# client.net
KiCad netlist of a schematic drawn in Altium Designer
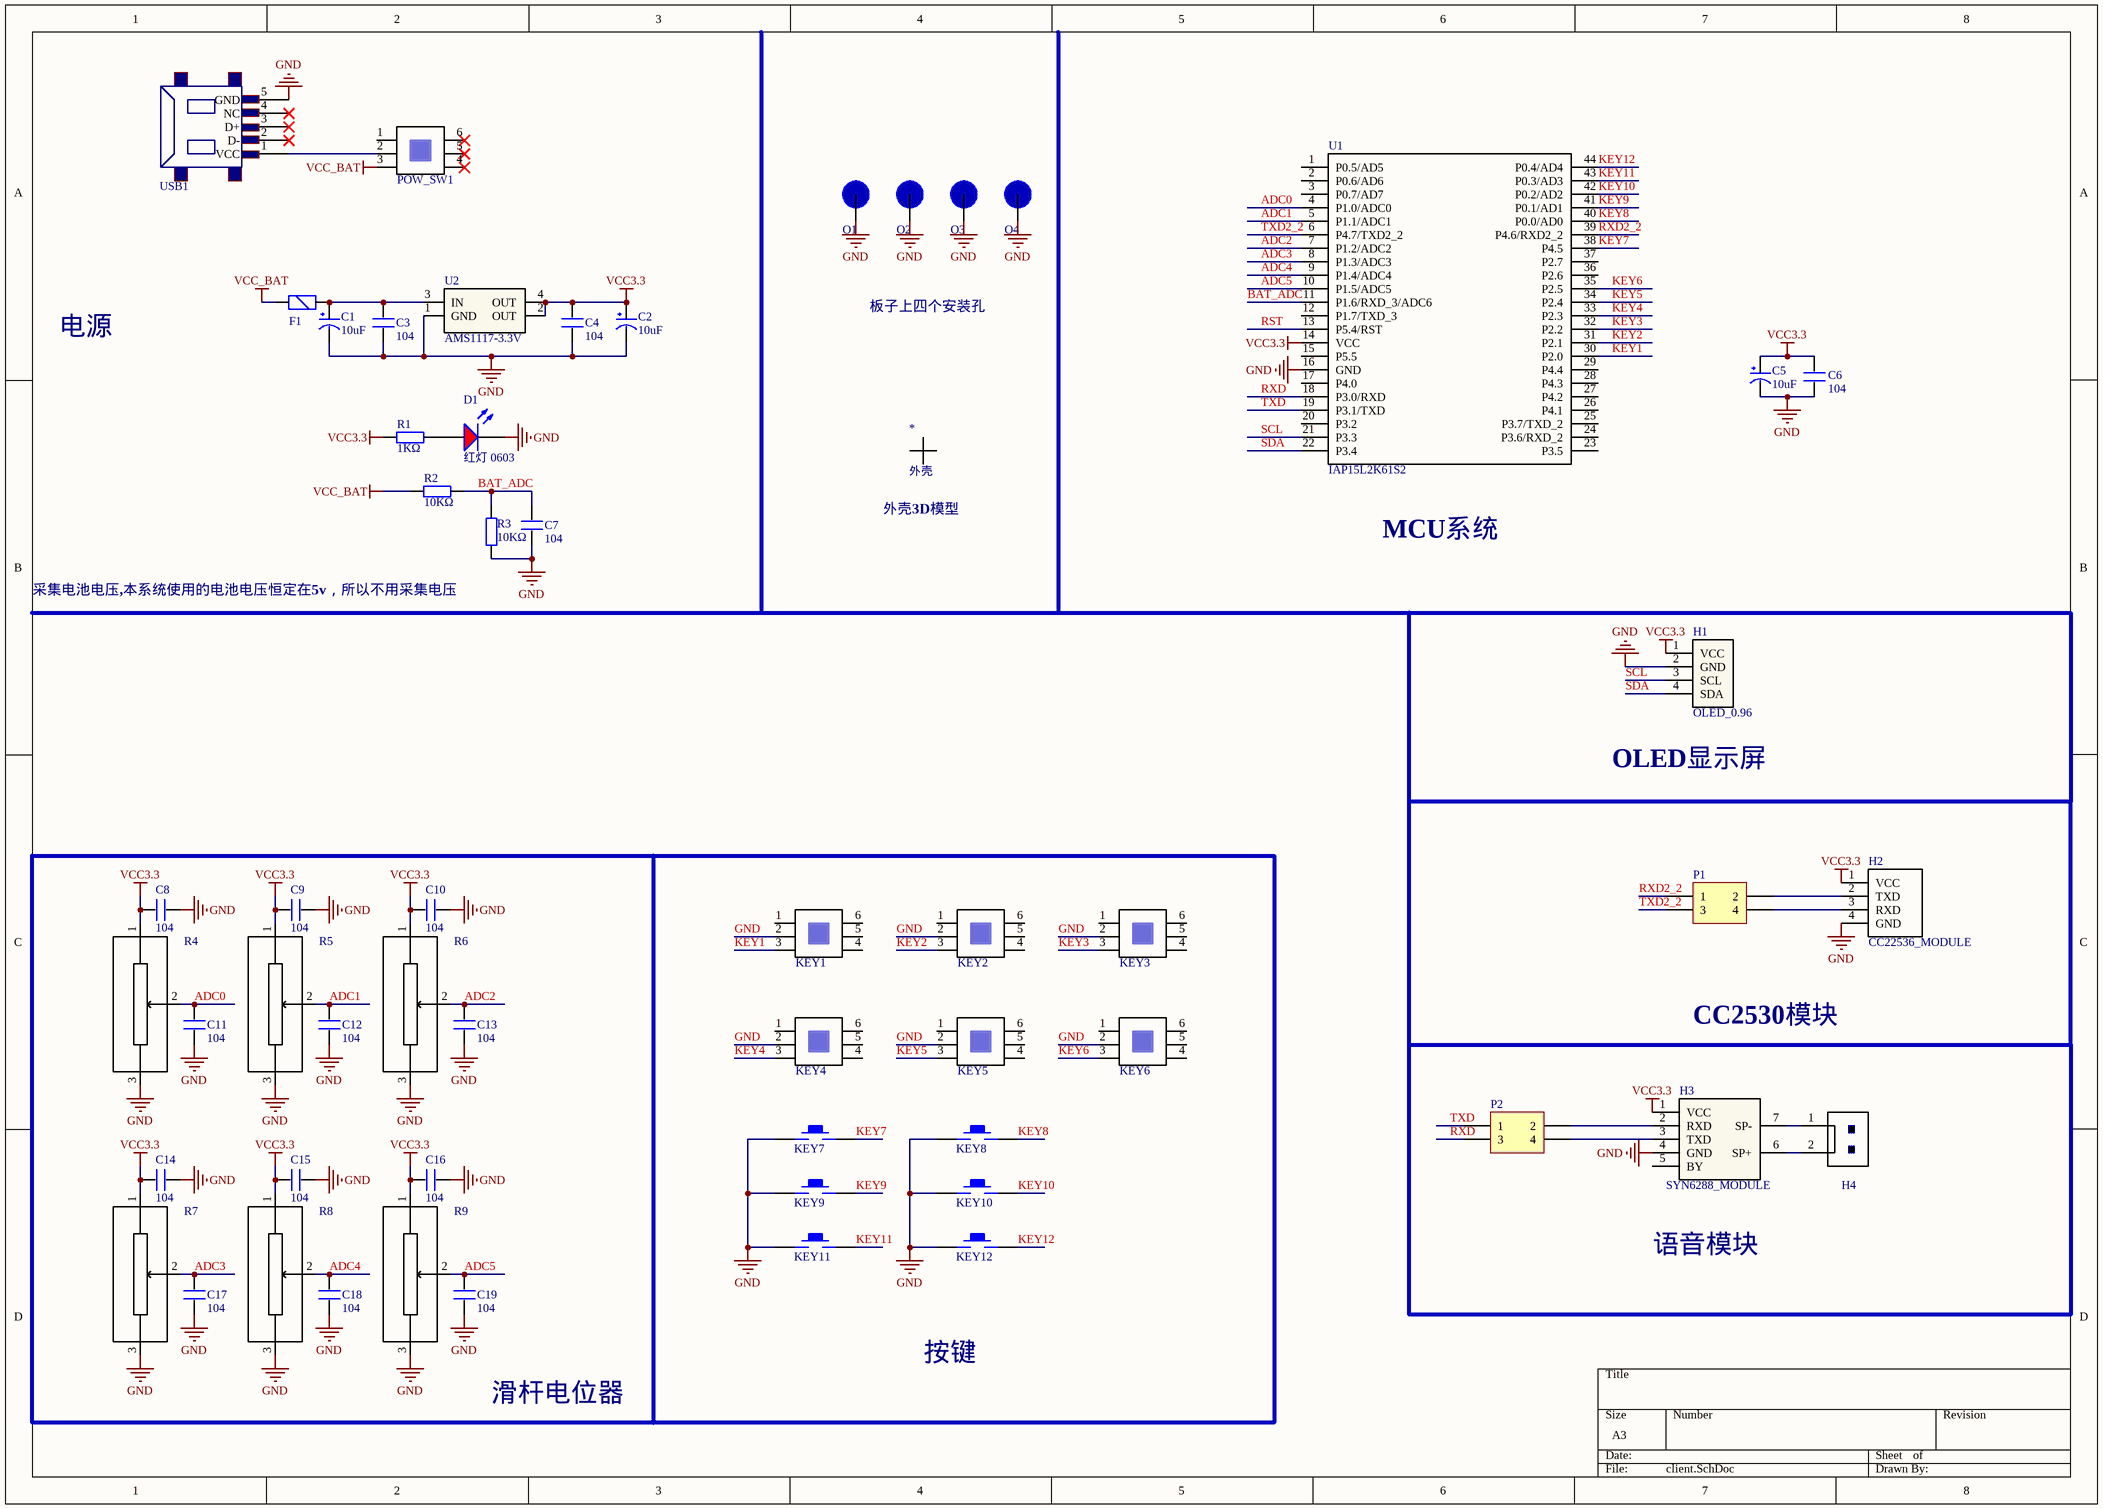
[diagram p0: client.SchDoc]

(export (version "E")
  (design (tool "Eeschema 10.0.6"))
  (components
    (comp (ref "*") (value "外壳") (footprint "MYLIB:外壳") (libsource (lib "mylib") (part "外壳")))
    (comp (ref "C1")
      (value "10uF")
      (footprint "3D common:C4X4")
      (libsource (lib "WarShip V3 STM32103封装库") (part "CAP"))
    )
    (comp (ref "C2")
      (value "10uF")
      (footprint "3D common:C4X4")
      (libsource (lib "WarShip V3 STM32103封装库") (part "CAP"))
    )
    (comp (ref "C3")
      (value "104")
      (footprint "嘉立创库:0603_C")
      (libsource (lib "WarShip V3 STM32103封装库") (part "C"))
    )
    (comp (ref "C4")
      (value "104")
      (footprint "嘉立创库:0603_C")
      (libsource (lib "WarShip V3 STM32103封装库") (part "C"))
    )
    (comp (ref "C5")
      (value "10uF")
      (footprint "3D common:C4X4")
      (libsource (lib "WarShip V3 STM32103封装库") (part "CAP"))
    )
    (comp (ref "C6")
      (value "104")
      (footprint "嘉立创库:0603_C")
      (libsource (lib "WarShip V3 STM32103封装库") (part "C"))
    )
    (comp (ref "C7")
      (value "104")
      (footprint "嘉立创库:0603_C")
      (libsource (lib "WarShip V3 STM32103封装库") (part "C"))
    )
    (comp (ref "C8") (value "104") (footprint "嘉立创库:0603_C") (libsource (lib "WARSHIP") (part "C")))
    (comp (ref "C9") (value "104") (footprint "嘉立创库:0603_C") (libsource (lib "WARSHIP") (part "C")))
    (comp (ref "C10") (value "104") (footprint "嘉立创库:0603_C") (libsource (lib "WARSHIP") (part "C")))
    (comp (ref "C11") (value "104") (footprint "嘉立创库:0603_C") (libsource (lib "WARSHIP") (part "C")))
    (comp (ref "C12") (value "104") (footprint "嘉立创库:0603_C") (libsource (lib "WARSHIP") (part "C")))
    (comp (ref "C13") (value "104") (footprint "嘉立创库:0603_C") (libsource (lib "WARSHIP") (part "C")))
    (comp (ref "C14") (value "104") (footprint "嘉立创库:0603_C") (libsource (lib "WARSHIP") (part "C")))
    (comp (ref "C15") (value "104") (footprint "嘉立创库:0603_C") (libsource (lib "WARSHIP") (part "C")))
    (comp (ref "C16") (value "104") (footprint "嘉立创库:0603_C") (libsource (lib "WARSHIP") (part "C")))
    (comp (ref "C17") (value "104") (footprint "嘉立创库:0603_C") (libsource (lib "WARSHIP") (part "C")))
    (comp (ref "C18") (value "104") (footprint "嘉立创库:0603_C") (libsource (lib "WARSHIP") (part "C")))
    (comp (ref "C19") (value "104") (footprint "嘉立创库:0603_C") (libsource (lib "WARSHIP") (part "C")))
    (comp (ref "D1")
      (value "红灯 0603")
      (footprint "0603_LED_S1")
      (description "发光二极管")
      (libsource (lib "嘉立创库") (part "0603 红灯"))
    )
    (comp (ref "F1") (value "F1") (footprint "MYLIB:Fuse1210") (libsource (lib "mylib") (part "Fuse")))
    (comp (ref "H1")
      (value "OLED_0.96")
      (footprint "WARSHIP:HDR1X4")
      (libsource (lib "mylib") (part "OLED_0.96"))
    )
    (comp (ref "H2")
      (value "CC22536_MODULE")
      (footprint "WARSHIP:HDR1X4")
      (libsource (lib "mylib") (part "CC22536_MODULE"))
    )
    (comp (ref "H3")
      (value "SYN6288_MODULE")
      (footprint "SYN6288_MODULE")
      (libsource (lib "mylib") (part "SYN6288_MODULE"))
    )
    (comp (ref "H4")
      (value "排插2*1")
      (footprint "MYLIB:XH2.54mm_2*1")
      (libsource (lib "mylib") (part "排插2*1"))
    )
    (comp (ref "KEY1")
      (value "switch6pin")
      (footprint "MYLIB:SWITCH_6PIN_8*8mm")
      (libsource (lib "mylib") (part "switch6pin"))
    )
    (comp (ref "KEY2")
      (value "switch6pin")
      (footprint "MYLIB:SWITCH_6PIN_8*8mm")
      (libsource (lib "mylib") (part "switch6pin"))
    )
    (comp (ref "KEY3")
      (value "switch6pin")
      (footprint "MYLIB:SWITCH_6PIN_8*8mm")
      (libsource (lib "mylib") (part "switch6pin"))
    )
    (comp (ref "KEY4")
      (value "switch6pin")
      (footprint "MYLIB:SWITCH_6PIN_8*8mm")
      (libsource (lib "mylib") (part "switch6pin"))
    )
    (comp (ref "KEY5")
      (value "switch6pin")
      (footprint "MYLIB:SWITCH_6PIN_8*8mm")
      (libsource (lib "mylib") (part "switch6pin"))
    )
    (comp (ref "KEY6")
      (value "switch6pin")
      (footprint "MYLIB:SWITCH_6PIN_8*8mm")
      (libsource (lib "mylib") (part "switch6pin"))
    )
    (comp (ref "KEY7")
      (value "KEY_M")
      (footprint "MYLIB:KEY_SMD_6*6*12mm")
      (libsource (lib "WARSHIP") (part "KEY_M"))
    )
    (comp (ref "KEY8")
      (value "KEY_M")
      (footprint "MYLIB:KEY_SMD_6*6*12mm")
      (libsource (lib "WARSHIP") (part "KEY_M"))
    )
    (comp (ref "KEY9")
      (value "KEY_M")
      (footprint "MYLIB:KEY_SMD_6*6*12mm")
      (libsource (lib "WARSHIP") (part "KEY_M"))
    )
    (comp (ref "KEY10")
      (value "KEY_M")
      (footprint "MYLIB:KEY_SMD_6*6*12mm")
      (libsource (lib "WARSHIP") (part "KEY_M"))
    )
    (comp (ref "KEY11")
      (value "KEY_M")
      (footprint "MYLIB:KEY_SMD_6*6*12mm")
      (libsource (lib "WARSHIP") (part "KEY_M"))
    )
    (comp (ref "KEY12")
      (value "KEY_M")
      (footprint "MYLIB:KEY_SMD_6*6*12mm")
      (libsource (lib "WARSHIP") (part "KEY_M"))
    )
    (comp (ref "O1") (value "安装孔3mm") (libsource (lib "mylib") (part "安装孔3mm")))
    (comp (ref "O2") (value "安装孔3mm") (libsource (lib "mylib") (part "安装孔3mm")))
    (comp (ref "O3") (value "安装孔3mm") (libsource (lib "mylib") (part "安装孔3mm")))
    (comp (ref "O4") (value "安装孔3mm") (libsource (lib "mylib") (part "安装孔3mm")))
    (comp (ref "P1")
      (value "~")
      (footprint "HDR2X2")
      (description "Header, 2-Pin, Dual row")
      (fields (field (name "PUBLISHER") "Altium Limited"))
      (libsource (lib "WARSHIP") (part "Header 2X2"))
    )
    (comp (ref "P2")
      (value "~")
      (footprint "HDR2X2")
      (description "Header, 2-Pin, Dual row")
      (fields (field (name "PUBLISHER") "Altium Limited"))
      (libsource (lib "WARSHIP") (part "Header 2X2"))
    )
    (comp (ref "POW_SW1")
      (value "switch6pin")
      (footprint "MYLIB:SWITCH_6PIN_8*8mm")
      (libsource (lib "mylib") (part "switch6pin"))
    )
    (comp (ref "R1")
      (value "1KΩ")
      (footprint "0603_R")
      (description "贴片电阻")
      (libsource (lib "嘉立创库") (part "0603 1KΩ (1001) 1%"))
    )
    (comp (ref "R2")
      (value "10KΩ")
      (footprint "0603_R")
      (description "贴片电阻")
      (libsource (lib "嘉立创库") (part "0603 1KΩ (1001) 1%"))
    )
    (comp (ref "R3")
      (value "10KΩ")
      (footprint "0603_R")
      (description "贴片电阻")
      (libsource (lib "") (part "0603 1KΩ (1001) 1%_1"))
    )
    (comp (ref "R4") (value "滑杆电位器") (footprint "滑杆电位器128mm") (libsource (lib "mylib") (part "滑杆电位器")))
    (comp (ref "R5") (value "滑杆电位器") (footprint "滑杆电位器128mm") (libsource (lib "mylib") (part "滑杆电位器")))
    (comp (ref "R6") (value "滑杆电位器") (footprint "滑杆电位器128mm") (libsource (lib "mylib") (part "滑杆电位器")))
    (comp (ref "R7") (value "滑杆电位器") (footprint "滑杆电位器128mm") (libsource (lib "mylib") (part "滑杆电位器")))
    (comp (ref "R8") (value "滑杆电位器") (footprint "滑杆电位器128mm") (libsource (lib "mylib") (part "滑杆电位器")))
    (comp (ref "R9") (value "滑杆电位器") (footprint "滑杆电位器128mm") (libsource (lib "mylib") (part "滑杆电位器")))
    (comp (ref "U1")
      (value "IAP15L2K61S2")
      (footprint "3D_1:LQFP44")
      (libsource (lib "mylib") (part "IAP15L2K61S2"))
    )
    (comp (ref "U2")
      (value "AMS1117-3.3V")
      (footprint "3D common:SOT-223")
      (libsource (lib "mylib") (part "AMS1117"))
    )
    (comp (ref "USB1")
      (value "USB1")
      (footprint "MYLIB:USB_MK5P")
      (libsource (lib "mylib") (part "USB-5PIN"))
    )
  )
  (nets
    (net (code "1") (name "/ADC0") (class "Default")
      (node (ref "C11") (pin "1") (pintype "passive"))
      (node (ref "R4") (pin "2") (pinfunction "2_2") (pintype "passive"))
      (node (ref "U1") (pin "4") (pinfunction "P1.0/ADC0_4") (pintype "passive"))
    )
    (net (code "2") (name "/ADC1") (class "Default")
      (node (ref "C12") (pin "1") (pintype "passive"))
      (node (ref "R5") (pin "2") (pinfunction "2_2") (pintype "passive"))
      (node (ref "U1") (pin "5") (pinfunction "P1.1/ADC1_5") (pintype "passive"))
    )
    (net (code "3") (name "/ADC2") (class "Default")
      (node (ref "C13") (pin "1") (pintype "passive"))
      (node (ref "R6") (pin "2") (pinfunction "2_2") (pintype "passive"))
      (node (ref "U1") (pin "7") (pinfunction "P1.2/ADC2_7") (pintype "passive"))
    )
    (net (code "4") (name "/ADC3") (class "Default")
      (node (ref "C17") (pin "1") (pintype "passive"))
      (node (ref "R7") (pin "2") (pinfunction "2_2") (pintype "passive"))
      (node (ref "U1") (pin "8") (pinfunction "P1.3/ADC3_8") (pintype "passive"))
    )
    (net (code "5") (name "/ADC4") (class "Default")
      (node (ref "C18") (pin "1") (pintype "passive"))
      (node (ref "R8") (pin "2") (pinfunction "2_2") (pintype "passive"))
      (node (ref "U1") (pin "9") (pinfunction "P1.4/ADC4_9") (pintype "passive"))
    )
    (net (code "6") (name "/ADC5") (class "Default")
      (node (ref "C19") (pin "1") (pintype "passive"))
      (node (ref "R9") (pin "2") (pinfunction "2_2") (pintype "passive"))
      (node (ref "U1") (pin "10") (pinfunction "P1.5/ADC5_10") (pintype "passive"))
    )
    (net (code "7") (name "/BAT_ADC") (class "Default")
      (node (ref "C7") (pin "1") (pintype "passive"))
      (node (ref "R2") (pin "2") (pinfunction "2_2") (pintype "passive"))
      (node (ref "R3") (pin "2") (pinfunction "2_2") (pintype "passive"))
      (node (ref "U1") (pin "11") (pinfunction "P1.6/RXD_3/ADC6_11") (pintype "passive"))
    )
    (net (code "8") (name "/KEY1") (class "Default")
      (node (ref "KEY1") (pin "3") (pinfunction "3_3") (pintype "passive"))
      (node (ref "U1") (pin "30") (pinfunction "P2.0_30") (pintype "passive"))
    )
    (net (code "9") (name "/KEY2") (class "Default")
      (node (ref "KEY2") (pin "3") (pinfunction "3_3") (pintype "passive"))
      (node (ref "U1") (pin "31") (pinfunction "P2.1_31") (pintype "passive"))
    )
    (net (code "10") (name "/KEY3") (class "Default")
      (node (ref "KEY3") (pin "3") (pinfunction "3_3") (pintype "passive"))
      (node (ref "U1") (pin "32") (pinfunction "P2.2_32") (pintype "passive"))
    )
    (net (code "11") (name "/KEY4") (class "Default")
      (node (ref "KEY4") (pin "3") (pinfunction "3_3") (pintype "passive"))
      (node (ref "U1") (pin "33") (pinfunction "P2.3_33") (pintype "passive"))
    )
    (net (code "12") (name "/KEY5") (class "Default")
      (node (ref "KEY5") (pin "3") (pinfunction "3_3") (pintype "passive"))
      (node (ref "U1") (pin "34") (pinfunction "P2.4_34") (pintype "passive"))
    )
    (net (code "13") (name "/KEY6") (class "Default")
      (node (ref "KEY6") (pin "3") (pinfunction "3_3") (pintype "passive"))
      (node (ref "U1") (pin "35") (pinfunction "P2.5_35") (pintype "passive"))
    )
    (net (code "14") (name "/KEY7") (class "Default")
      (node (ref "KEY7") (pin "2") (pinfunction "2_2") (pintype "passive"))
      (node (ref "U1") (pin "38") (pinfunction "P4.5_38") (pintype "passive"))
    )
    (net (code "15") (name "/KEY8") (class "Default")
      (node (ref "KEY8") (pin "2") (pinfunction "2_2") (pintype "passive"))
      (node (ref "U1") (pin "40") (pinfunction "P0.0/AD0_40") (pintype "passive"))
    )
    (net (code "16") (name "/KEY9") (class "Default")
      (node (ref "KEY9") (pin "2") (pinfunction "2_2") (pintype "passive"))
      (node (ref "U1") (pin "41") (pinfunction "P0.1/AD1_41") (pintype "passive"))
    )
    (net (code "17") (name "/KEY10") (class "Default")
      (node (ref "KEY10") (pin "2") (pinfunction "2_2") (pintype "passive"))
      (node (ref "U1") (pin "42") (pinfunction "P0.2/AD2_42") (pintype "passive"))
    )
    (net (code "18") (name "/KEY11") (class "Default")
      (node (ref "KEY11") (pin "2") (pinfunction "2_2") (pintype "passive"))
      (node (ref "U1") (pin "43") (pinfunction "P0.3/AD3_43") (pintype "passive"))
    )
    (net (code "19") (name "/KEY12") (class "Default")
      (node (ref "KEY12") (pin "2") (pinfunction "2_2") (pintype "passive"))
      (node (ref "U1") (pin "44") (pinfunction "P0.4/AD4_44") (pintype "passive"))
    )
    (net (code "20") (name "/RST") (class "Default")
      (node (ref "U1") (pin "13") (pinfunction "P5.4/RST_13") (pintype "passive"))
    )
    (net (code "21") (name "/RXD") (class "Default")
      (node (ref "P2") (pin "3") (pinfunction "3_3") (pintype "passive"))
      (node (ref "U1") (pin "18") (pinfunction "P3.0/RXD_18") (pintype "passive"))
    )
    (net (code "22") (name "/RXD2_2") (class "Default")
      (node (ref "P1") (pin "1") (pinfunction "1_1") (pintype "passive"))
      (node (ref "U1") (pin "39") (pinfunction "P4.6/RXD2_2_39") (pintype "passive"))
    )
    (net (code "23") (name "/SCL") (class "Default")
      (node (ref "H1") (pin "3") (pinfunction "SCL_3") (pintype "passive"))
      (node (ref "U1") (pin "21") (pinfunction "P3.3_21") (pintype "passive"))
    )
    (net (code "24") (name "/SDA") (class "Default")
      (node (ref "H1") (pin "4") (pinfunction "SDA_4") (pintype "passive"))
      (node (ref "U1") (pin "22") (pinfunction "P3.4_22") (pintype "passive"))
    )
    (net (code "25") (name "/TXD") (class "Default")
      (node (ref "P2") (pin "1") (pinfunction "1_1") (pintype "passive"))
      (node (ref "U1") (pin "19") (pinfunction "P3.1/TXD_19") (pintype "passive"))
    )
    (net (code "26") (name "/TXD2_2") (class "Default")
      (node (ref "P1") (pin "3") (pinfunction "3_3") (pintype "passive"))
      (node (ref "U1") (pin "6") (pinfunction "P4.7/TXD2_2_6") (pintype "passive"))
    )
    (net (code "27") (name "GND") (class "Default")
      (node (ref "C1") (pin "2") (pinfunction "GND_2") (pintype "passive"))
      (node (ref "C10") (pin "2") (pintype "passive"))
      (node (ref "C11") (pin "2") (pintype "passive"))
      (node (ref "C12") (pin "2") (pintype "passive"))
      (node (ref "C13") (pin "2") (pintype "passive"))
      (node (ref "C14") (pin "2") (pintype "passive"))
      (node (ref "C15") (pin "2") (pintype "passive"))
      (node (ref "C16") (pin "2") (pintype "passive"))
      (node (ref "C17") (pin "2") (pintype "passive"))
      (node (ref "C18") (pin "2") (pintype "passive"))
      (node (ref "C19") (pin "2") (pintype "passive"))
      (node (ref "C2") (pin "2") (pinfunction "GND_2") (pintype "passive"))
      (node (ref "C3") (pin "2") (pintype "passive"))
      (node (ref "C4") (pin "2") (pintype "passive"))
      (node (ref "C5") (pin "2") (pinfunction "GND_2") (pintype "passive"))
      (node (ref "C6") (pin "2") (pintype "passive"))
      (node (ref "C7") (pin "2") (pintype "passive"))
      (node (ref "C8") (pin "2") (pintype "passive"))
      (node (ref "C9") (pin "2") (pintype "passive"))
      (node (ref "D1") (pin "K") (pinfunction "K_K") (pintype "passive"))
      (node (ref "H1") (pin "2") (pinfunction "GND_2") (pintype "passive"))
      (node (ref "H2") (pin "4") (pinfunction "GND_4") (pintype "passive"))
      (node (ref "H3") (pin "4") (pinfunction "GND_4") (pintype "passive"))
      (node (ref "KEY1") (pin "2") (pinfunction "2_2") (pintype "passive"))
      (node (ref "KEY10") (pin "1") (pinfunction "1_1") (pintype "passive"))
      (node (ref "KEY11") (pin "1") (pinfunction "1_1") (pintype "passive"))
      (node (ref "KEY12") (pin "1") (pinfunction "1_1") (pintype "passive"))
      (node (ref "KEY2") (pin "2") (pinfunction "2_2") (pintype "passive"))
      (node (ref "KEY3") (pin "2") (pinfunction "2_2") (pintype "passive"))
      (node (ref "KEY4") (pin "2") (pinfunction "2_2") (pintype "passive"))
      (node (ref "KEY5") (pin "2") (pinfunction "2_2") (pintype "passive"))
      (node (ref "KEY6") (pin "2") (pinfunction "2_2") (pintype "passive"))
      (node (ref "KEY7") (pin "1") (pinfunction "1_1") (pintype "passive"))
      (node (ref "KEY8") (pin "1") (pinfunction "1_1") (pintype "passive"))
      (node (ref "KEY9") (pin "1") (pinfunction "1_1") (pintype "passive"))
      (node (ref "O1") (pin "0") (pinfunction "GND_0") (pintype "passive"))
      (node (ref "O2") (pin "0") (pinfunction "GND_0") (pintype "passive"))
      (node (ref "O3") (pin "0") (pinfunction "GND_0") (pintype "passive"))
      (node (ref "O4") (pin "0") (pinfunction "GND_0") (pintype "passive"))
      (node (ref "R3") (pin "1") (pinfunction "1_1") (pintype "passive"))
      (node (ref "R4") (pin "3") (pinfunction "3_3") (pintype "passive"))
      (node (ref "R5") (pin "3") (pinfunction "3_3") (pintype "passive"))
      (node (ref "R6") (pin "3") (pinfunction "3_3") (pintype "passive"))
      (node (ref "R7") (pin "3") (pinfunction "3_3") (pintype "passive"))
      (node (ref "R8") (pin "3") (pinfunction "3_3") (pintype "passive"))
      (node (ref "R9") (pin "3") (pinfunction "3_3") (pintype "passive"))
      (node (ref "U1") (pin "16") (pinfunction "GND_16") (pintype "passive"))
      (node (ref "U2") (pin "1") (pinfunction "GND_1") (pintype "passive"))
      (node (ref "USB1") (pin "5") (pinfunction "GND_5") (pintype "passive"))
    )
    (net (code "28") (name "Net-(C1-VCC)") (class "Default")
      (node (ref "C1") (pin "1") (pinfunction "VCC_1") (pintype "passive"))
      (node (ref "C3") (pin "1") (pintype "passive"))
      (node (ref "F1") (pin "1") (pinfunction "1_1") (pintype "passive"))
      (node (ref "U2") (pin "3") (pinfunction "IN_3") (pintype "passive"))
    )
    (net (code "29") (name "Net-(D1-PadA)") (class "Default")
      (node (ref "D1") (pin "A") (pinfunction "A_A") (pintype "passive"))
      (node (ref "R1") (pin "2") (pinfunction "2_2") (pintype "passive"))
    )
    (net (code "30") (name "Net-(H2-RXD)") (class "Default")
      (node (ref "H2") (pin "3") (pinfunction "RXD_3") (pintype "passive"))
      (node (ref "P1") (pin "4") (pinfunction "4_4") (pintype "passive"))
    )
    (net (code "31") (name "Net-(H2-TXD)") (class "Default")
      (node (ref "H2") (pin "2") (pinfunction "TXD_2") (pintype "passive"))
      (node (ref "P1") (pin "2") (pinfunction "2_2") (pintype "passive"))
    )
    (net (code "32") (name "Net-(H3-RXD)") (class "Default")
      (node (ref "H3") (pin "2") (pinfunction "RXD_2") (pintype "passive"))
      (node (ref "P2") (pin "2") (pinfunction "2_2") (pintype "passive"))
    )
    (net (code "33") (name "Net-(H3-SP+)") (class "Default")
      (node (ref "H3") (pin "6") (pinfunction "SP+_6") (pintype "passive"))
      (node (ref "H4") (pin "2") (pinfunction "SP+_2") (pintype "passive"))
    )
    (net (code "34") (name "Net-(H3-SP-)") (class "Default")
      (node (ref "H3") (pin "7") (pinfunction "SP-_7") (pintype "passive"))
      (node (ref "H4") (pin "1") (pinfunction "SP-_1") (pintype "passive"))
    )
    (net (code "35") (name "Net-(H3-TXD)") (class "Default")
      (node (ref "H3") (pin "3") (pinfunction "TXD_3") (pintype "passive"))
      (node (ref "P2") (pin "4") (pinfunction "4_4") (pintype "passive"))
    )
    (net (code "36") (name "Net-(USB1-VCC)") (class "Default")
      (node (ref "POW_SW1") (pin "2") (pinfunction "2_2") (pintype "passive"))
      (node (ref "USB1") (pin "1") (pinfunction "VCC_1") (pintype "passive"))
    )
    (net (code "37") (name "VCC3.3") (class "Default")
      (node (ref "C10") (pin "1") (pintype "passive"))
      (node (ref "C14") (pin "1") (pintype "passive"))
      (node (ref "C15") (pin "1") (pintype "passive"))
      (node (ref "C16") (pin "1") (pintype "passive"))
      (node (ref "C2") (pin "1") (pinfunction "VCC_1") (pintype "passive"))
      (node (ref "C4") (pin "1") (pintype "passive"))
      (node (ref "C5") (pin "1") (pinfunction "VCC_1") (pintype "passive"))
      (node (ref "C6") (pin "1") (pintype "passive"))
      (node (ref "C8") (pin "1") (pintype "passive"))
      (node (ref "C9") (pin "1") (pintype "passive"))
      (node (ref "H1") (pin "1") (pinfunction "VCC_1") (pintype "passive"))
      (node (ref "H2") (pin "1") (pinfunction "VCC_1") (pintype "passive"))
      (node (ref "H3") (pin "1") (pinfunction "VCC_1") (pintype "passive"))
      (node (ref "R1") (pin "1") (pinfunction "1_1") (pintype "passive"))
      (node (ref "R4") (pin "1") (pinfunction "1_1") (pintype "passive"))
      (node (ref "R5") (pin "1") (pinfunction "1_1") (pintype "passive"))
      (node (ref "R6") (pin "1") (pinfunction "1_1") (pintype "passive"))
      (node (ref "R7") (pin "1") (pinfunction "1_1") (pintype "passive"))
      (node (ref "R8") (pin "1") (pinfunction "1_1") (pintype "passive"))
      (node (ref "R9") (pin "1") (pinfunction "1_1") (pintype "passive"))
      (node (ref "U1") (pin "14") (pinfunction "VCC_14") (pintype "passive"))
      (node (ref "U2") (pin "2") (pinfunction "OUT_2") (pintype "passive"))
      (node (ref "U2") (pin "4") (pinfunction "OUT_4") (pintype "passive"))
    )
    (net (code "38") (name "VCC_BAT") (class "Default")
      (node (ref "F1") (pin "2") (pinfunction "2_2") (pintype "passive"))
      (node (ref "POW_SW1") (pin "3") (pinfunction "3_3") (pintype "passive"))
      (node (ref "R2") (pin "1") (pinfunction "1_1") (pintype "passive"))
    )
    (net (code "39") (name "unconnected-(H3-BY-Pad5)") (class "Default")
      (node (ref "H3") (pin "5") (pinfunction "BY_5") (pintype "passive"))
    )
    (net (code "40") (name "unconnected-(KEY1-Pad1)") (class "Default")
      (node (ref "KEY1") (pin "1") (pinfunction "1_1") (pintype "passive"))
    )
    (net (code "41") (name "unconnected-(KEY1-Pad4)") (class "Default")
      (node (ref "KEY1") (pin "4") (pinfunction "4_4") (pintype "passive"))
    )
    (net (code "42") (name "unconnected-(KEY1-Pad5)") (class "Default")
      (node (ref "KEY1") (pin "5") (pinfunction "5_5") (pintype "passive"))
    )
    (net (code "43") (name "unconnected-(KEY1-Pad6)") (class "Default")
      (node (ref "KEY1") (pin "6") (pinfunction "6_6") (pintype "passive"))
    )
    (net (code "44") (name "unconnected-(KEY2-Pad1)") (class "Default")
      (node (ref "KEY2") (pin "1") (pinfunction "1_1") (pintype "passive"))
    )
    (net (code "45") (name "unconnected-(KEY2-Pad4)") (class "Default")
      (node (ref "KEY2") (pin "4") (pinfunction "4_4") (pintype "passive"))
    )
    (net (code "46") (name "unconnected-(KEY2-Pad5)") (class "Default")
      (node (ref "KEY2") (pin "5") (pinfunction "5_5") (pintype "passive"))
    )
    (net (code "47") (name "unconnected-(KEY2-Pad6)") (class "Default")
      (node (ref "KEY2") (pin "6") (pinfunction "6_6") (pintype "passive"))
    )
    (net (code "48") (name "unconnected-(KEY3-Pad1)") (class "Default")
      (node (ref "KEY3") (pin "1") (pinfunction "1_1") (pintype "passive"))
    )
    (net (code "49") (name "unconnected-(KEY3-Pad4)") (class "Default")
      (node (ref "KEY3") (pin "4") (pinfunction "4_4") (pintype "passive"))
    )
    (net (code "50") (name "unconnected-(KEY3-Pad5)") (class "Default")
      (node (ref "KEY3") (pin "5") (pinfunction "5_5") (pintype "passive"))
    )
    (net (code "51") (name "unconnected-(KEY3-Pad6)") (class "Default")
      (node (ref "KEY3") (pin "6") (pinfunction "6_6") (pintype "passive"))
    )
    (net (code "52") (name "unconnected-(KEY4-Pad1)") (class "Default")
      (node (ref "KEY4") (pin "1") (pinfunction "1_1") (pintype "passive"))
    )
    (net (code "53") (name "unconnected-(KEY4-Pad4)") (class "Default")
      (node (ref "KEY4") (pin "4") (pinfunction "4_4") (pintype "passive"))
    )
    (net (code "54") (name "unconnected-(KEY4-Pad5)") (class "Default")
      (node (ref "KEY4") (pin "5") (pinfunction "5_5") (pintype "passive"))
    )
    (net (code "55") (name "unconnected-(KEY4-Pad6)") (class "Default")
      (node (ref "KEY4") (pin "6") (pinfunction "6_6") (pintype "passive"))
    )
    (net (code "56") (name "unconnected-(KEY5-Pad1)") (class "Default")
      (node (ref "KEY5") (pin "1") (pinfunction "1_1") (pintype "passive"))
    )
    (net (code "57") (name "unconnected-(KEY5-Pad4)") (class "Default")
      (node (ref "KEY5") (pin "4") (pinfunction "4_4") (pintype "passive"))
    )
    (net (code "58") (name "unconnected-(KEY5-Pad5)") (class "Default")
      (node (ref "KEY5") (pin "5") (pinfunction "5_5") (pintype "passive"))
    )
    (net (code "59") (name "unconnected-(KEY5-Pad6)") (class "Default")
      (node (ref "KEY5") (pin "6") (pinfunction "6_6") (pintype "passive"))
    )
    (net (code "60") (name "unconnected-(KEY6-Pad1)") (class "Default")
      (node (ref "KEY6") (pin "1") (pinfunction "1_1") (pintype "passive"))
    )
    (net (code "61") (name "unconnected-(KEY6-Pad4)") (class "Default")
      (node (ref "KEY6") (pin "4") (pinfunction "4_4") (pintype "passive"))
    )
    (net (code "62") (name "unconnected-(KEY6-Pad5)") (class "Default")
      (node (ref "KEY6") (pin "5") (pinfunction "5_5") (pintype "passive"))
    )
    (net (code "63") (name "unconnected-(KEY6-Pad6)") (class "Default")
      (node (ref "KEY6") (pin "6") (pinfunction "6_6") (pintype "passive"))
    )
    (net (code "64") (name "unconnected-(POW_SW1-Pad1)") (class "Default")
      (node (ref "POW_SW1") (pin "1") (pinfunction "1_1") (pintype "passive"))
    )
    (net (code "65") (name "unconnected-(POW_SW1-Pad4)") (class "Default")
      (node (ref "POW_SW1") (pin "4") (pinfunction "4_4") (pintype "passive+no_connect"))
    )
    (net (code "66") (name "unconnected-(POW_SW1-Pad5)") (class "Default")
      (node (ref "POW_SW1") (pin "5") (pinfunction "5_5") (pintype "passive+no_connect"))
    )
    (net (code "67") (name "unconnected-(POW_SW1-Pad6)") (class "Default")
      (node (ref "POW_SW1") (pin "6") (pinfunction "6_6") (pintype "passive+no_connect"))
    )
    (net (code "68") (name "unconnected-(U1-P0.5{slash}AD5-Pad1)") (class "Default")
      (node (ref "U1") (pin "1") (pinfunction "P0.5/AD5_1") (pintype "passive"))
    )
    (net (code "69") (name "unconnected-(U1-P0.6{slash}AD6-Pad2)") (class "Default")
      (node (ref "U1") (pin "2") (pinfunction "P0.6/AD6_2") (pintype "passive"))
    )
    (net (code "70") (name "unconnected-(U1-P0.7{slash}AD7-Pad3)") (class "Default")
      (node (ref "U1") (pin "3") (pinfunction "P0.7/AD7_3") (pintype "passive"))
    )
    (net (code "71") (name "unconnected-(U1-P1.7{slash}TXD_3-Pad12)") (class "Default")
      (node (ref "U1") (pin "12") (pinfunction "P1.7/TXD_3_12") (pintype "passive"))
    )
    (net (code "72") (name "unconnected-(U1-P2.6-Pad36)") (class "Default")
      (node (ref "U1") (pin "36") (pinfunction "P2.6_36") (pintype "passive"))
    )
    (net (code "73") (name "unconnected-(U1-P2.7-Pad37)") (class "Default")
      (node (ref "U1") (pin "37") (pinfunction "P2.7_37") (pintype "passive"))
    )
    (net (code "74") (name "unconnected-(U1-P3.2-Pad20)") (class "Default")
      (node (ref "U1") (pin "20") (pinfunction "P3.2_20") (pintype "passive"))
    )
    (net (code "75") (name "unconnected-(U1-P3.5-Pad23)") (class "Default")
      (node (ref "U1") (pin "23") (pinfunction "P3.5_23") (pintype "passive"))
    )
    (net (code "76") (name "unconnected-(U1-P3.6{slash}RXD_2-Pad24)") (class "Default")
      (node (ref "U1") (pin "24") (pinfunction "P3.6/RXD_2_24") (pintype "passive"))
    )
    (net (code "77") (name "unconnected-(U1-P3.7{slash}TXD_2-Pad25)") (class "Default")
      (node (ref "U1") (pin "25") (pinfunction "P3.7/TXD_2_25") (pintype "passive"))
    )
    (net (code "78") (name "unconnected-(U1-P4.0-Pad17)") (class "Default")
      (node (ref "U1") (pin "17") (pinfunction "P4.0_17") (pintype "passive"))
    )
    (net (code "79") (name "unconnected-(U1-P4.1-Pad26)") (class "Default")
      (node (ref "U1") (pin "26") (pinfunction "P4.1_26") (pintype "passive"))
    )
    (net (code "80") (name "unconnected-(U1-P4.2-Pad27)") (class "Default")
      (node (ref "U1") (pin "27") (pinfunction "P4.2_27") (pintype "passive"))
    )
    (net (code "81") (name "unconnected-(U1-P4.3-Pad28)") (class "Default")
      (node (ref "U1") (pin "28") (pinfunction "P4.3_28") (pintype "passive"))
    )
    (net (code "82") (name "unconnected-(U1-P4.4-Pad29)") (class "Default")
      (node (ref "U1") (pin "29") (pinfunction "P4.4_29") (pintype "passive"))
    )
    (net (code "83") (name "unconnected-(U1-P5.5-Pad15)") (class "Default")
      (node (ref "U1") (pin "15") (pinfunction "P5.5_15") (pintype "passive"))
    )
    (net (code "84") (name "unconnected-(USB1-D+-Pad3)") (class "Default")
      (node (ref "USB1") (pin "3") (pinfunction "D+_3") (pintype "passive+no_connect"))
    )
    (net (code "85") (name "unconnected-(USB1-D--Pad2)") (class "Default")
      (node (ref "USB1") (pin "2") (pinfunction "D-_2") (pintype "passive+no_connect"))
    )
    (net (code "86") (name "unconnected-(USB1-NC-Pad4)") (class "Default")
      (node (ref "USB1") (pin "4") (pinfunction "NC_4") (pintype "passive+no_connect"))
    )
  )
)
